# wifiuart_03_12_2018.net
KiCad netlist of a schematic drawn in EAGLE
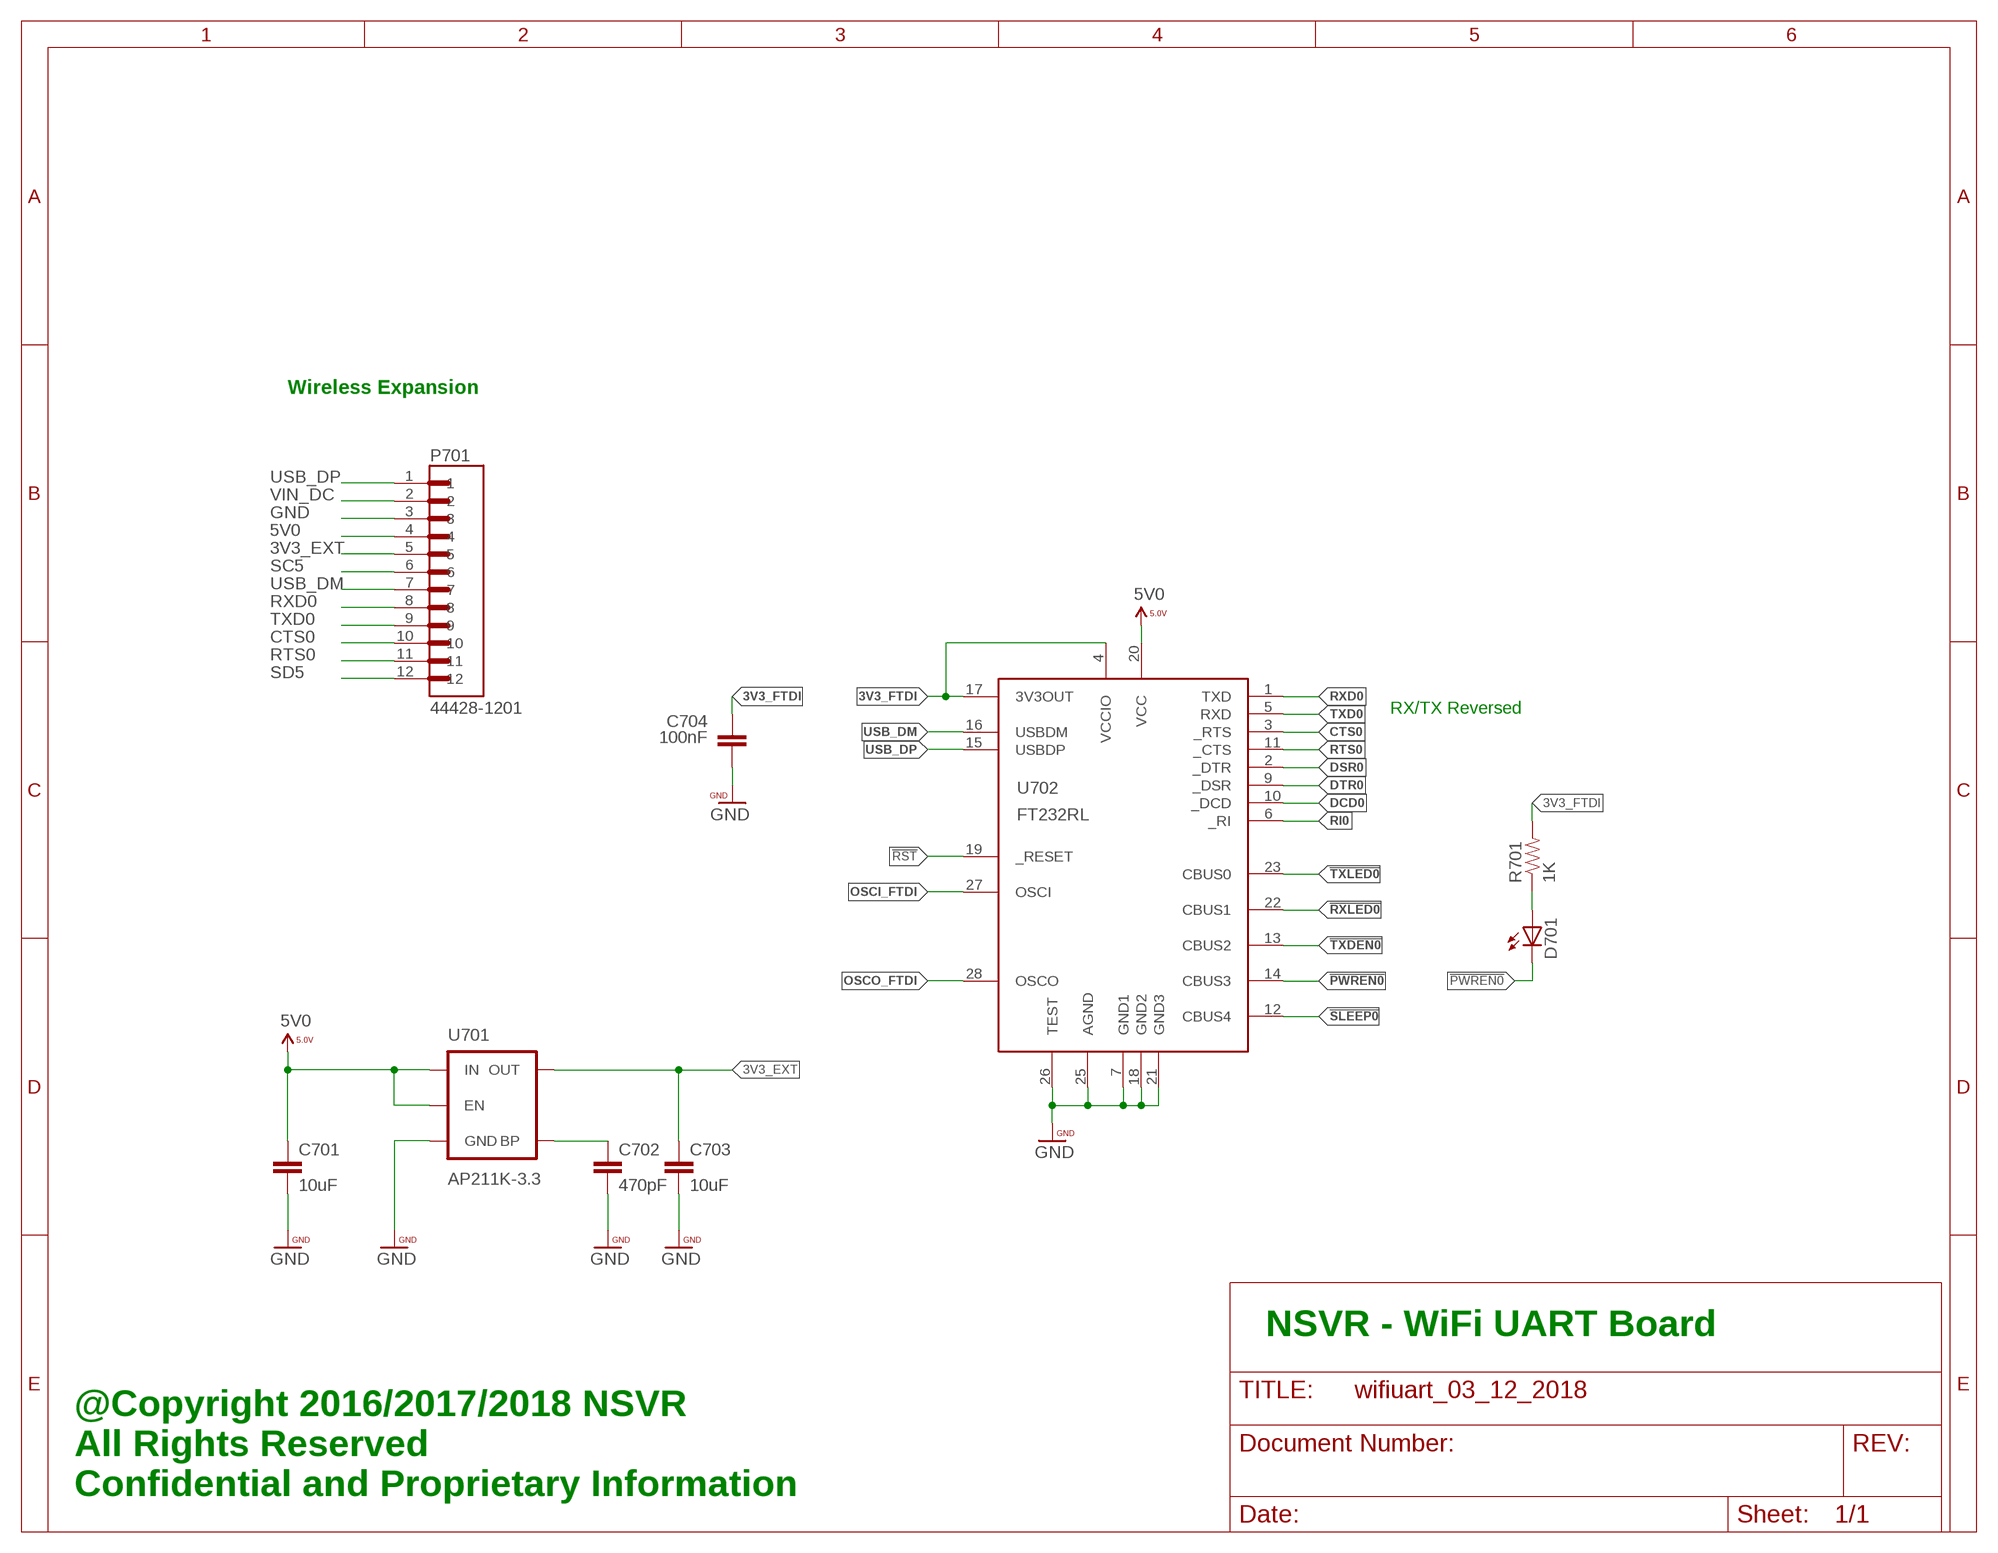
[diagram p0: schematic, sheet 1]

(export (version "E")
  (design (tool "Eeschema 10.0.6"))
  (components
    (comp (ref "C701")
      (value "10uF")
      (footprint "eagle-import:0603-CAP")
      (libsource (lib "eagle-import") (part "CAP0603-CAP"))
    )
    (comp (ref "C702")
      (value "470pF")
      (footprint "eagle-import:0402-CAP")
      (libsource (lib "eagle-import") (part "CAP0402-CAP"))
    )
    (comp (ref "C703")
      (value "10uF")
      (footprint "eagle-import:0603-CAP")
      (libsource (lib "eagle-import") (part "CAP0603-CAP"))
    )
    (comp (ref "C704")
      (value "100nF")
      (footprint "eagle-import:0402-CAP")
      (libsource (lib "eagle-import") (part "CAP0402-CAP"))
    )
    (comp (ref "D701")
      (value "LEDCHIP-LED0603")
      (footprint "eagle-import:CHIP-LED0603")
      (libsource (lib "eagle-import") (part "LEDCHIP-LED0603"))
    )
    (comp (ref "P701")
      (value "44428-1201")
      (footprint "eagle-import:MOLEX_44428-1201")
      (fields (field (name "MF") "Molex"))
      (libsource (lib "eagle-import") (part "44428-1201"))
    )
    (comp (ref "R701")
      (value "1K")
      (footprint "eagle-import:EIA-0402")
      (libsource (lib "eagle-import") (part "RESISTOR0402-TYP"))
    )
    (comp (ref "U701")
      (value "AP211K-3.3")
      (footprint "eagle-import:SOT23-5")
      (libsource (lib "eagle-import") (part "V_REG_MIC52053.3V"))
    )
    (comp (ref "U702")
      (value "FT232RL")
      (footprint "eagle-import:SSOP28DB")
      (libsource (lib "eagle-import") (part "FT232RL"))
    )
  )
  (nets
    (net (code "1") (name "/SC5") (class "Default")
      (node (ref "P701") (pin "6") (pinfunction "6_6") (pintype "passive"))
    )
    (net (code "2") (name "/SD5") (class "Default")
      (node (ref "P701") (pin "12") (pinfunction "12_12") (pintype "passive"))
    )
    (net (code "3") (name "/VIN_DC") (class "Default")
      (node (ref "P701") (pin "2") (pinfunction "2_2") (pintype "passive"))
    )
    (net (code "4") (name "/~{PWREN0}") (class "Default")
      (node (ref "D701") (pin "C") (pinfunction "C_C") (pintype "passive"))
      (node (ref "U702") (pin "14") (pinfunction "CBUS3_14") (pintype "bidirectional"))
    )
    (net (code "5") (name "/~{RST}") (class "Default")
      (node (ref "U702") (pin "19") (pinfunction "_RESET_19") (pintype "input"))
    )
    (net (code "6") (name "/~{RXLED0}") (class "Default")
      (node (ref "U702") (pin "22") (pinfunction "CBUS1_22") (pintype "bidirectional"))
    )
    (net (code "7") (name "/~{SLEEP0}") (class "Default")
      (node (ref "U702") (pin "12") (pinfunction "CBUS4_12") (pintype "bidirectional"))
    )
    (net (code "8") (name "/~{TXDEN0}") (class "Default")
      (node (ref "U702") (pin "13") (pinfunction "CBUS2_13") (pintype "bidirectional"))
    )
    (net (code "9") (name "/~{TXLED0}") (class "Default")
      (node (ref "U702") (pin "23") (pinfunction "CBUS0_23") (pintype "bidirectional"))
    )
    (net (code "10") (name "3V3_EXT") (class "Default")
      (node (ref "C703") (pin "1") (pinfunction "1_1") (pintype "passive"))
      (node (ref "P701") (pin "5") (pinfunction "5_5") (pintype "passive"))
      (node (ref "U701") (pin "5") (pinfunction "OUT_5") (pintype "passive"))
    )
    (net (code "11") (name "3V3_FTDI") (class "Default")
      (node (ref "C704") (pin "1") (pinfunction "1_1") (pintype "passive"))
      (node (ref "R701") (pin "2") (pinfunction "2_2") (pintype "passive"))
      (node (ref "U702") (pin "17") (pinfunction "3V3OUT_17") (pintype "output"))
      (node (ref "U702") (pin "4") (pinfunction "VCCIO_4") (pintype "power_in"))
    )
    (net (code "12") (name "5V0") (class "Default")
      (node (ref "C701") (pin "1") (pinfunction "1_1") (pintype "passive"))
      (node (ref "P701") (pin "4") (pinfunction "4_4") (pintype "passive"))
      (node (ref "U701") (pin "1") (pinfunction "IN_1") (pintype "input"))
      (node (ref "U701") (pin "3") (pinfunction "EN_3") (pintype "input"))
      (node (ref "U702") (pin "20") (pinfunction "VCC_20") (pintype "power_in"))
    )
    (net (code "13") (name "CTS0") (class "Default")
      (node (ref "P701") (pin "10") (pinfunction "10_10") (pintype "passive"))
      (node (ref "U702") (pin "3") (pinfunction "_RTS_3") (pintype "output"))
    )
    (net (code "14") (name "DCD0") (class "Default")
      (node (ref "U702") (pin "10") (pinfunction "_DCD_10") (pintype "input"))
    )
    (net (code "15") (name "DSR0") (class "Default")
      (node (ref "U702") (pin "2") (pinfunction "_DTR_2") (pintype "output"))
    )
    (net (code "16") (name "DTR0") (class "Default")
      (node (ref "U702") (pin "9") (pinfunction "_DSR_9") (pintype "input"))
    )
    (net (code "17") (name "GND") (class "Default")
      (node (ref "C701") (pin "2") (pinfunction "2_2") (pintype "passive"))
      (node (ref "C702") (pin "2") (pinfunction "2_2") (pintype "passive"))
      (node (ref "C703") (pin "2") (pinfunction "2_2") (pintype "passive"))
      (node (ref "C704") (pin "2") (pinfunction "2_2") (pintype "passive"))
      (node (ref "P701") (pin "3") (pinfunction "3_3") (pintype "passive"))
      (node (ref "U701") (pin "2") (pinfunction "GND_2") (pintype "input"))
      (node (ref "U702") (pin "18") (pinfunction "GND2_18") (pintype "power_in"))
      (node (ref "U702") (pin "21") (pinfunction "GND3_21") (pintype "power_in"))
      (node (ref "U702") (pin "25") (pinfunction "AGND_25") (pintype "power_in"))
      (node (ref "U702") (pin "26") (pinfunction "TEST_26") (pintype "input"))
      (node (ref "U702") (pin "7") (pinfunction "GND1_7") (pintype "power_in"))
    )
    (net (code "18") (name "Net-(D701-PadA)") (class "Default")
      (node (ref "D701") (pin "A") (pinfunction "A_A") (pintype "passive"))
      (node (ref "R701") (pin "1") (pinfunction "1_1") (pintype "passive"))
    )
    (net (code "19") (name "Net-(U701-BP)") (class "Default")
      (node (ref "C702") (pin "1") (pinfunction "1_1") (pintype "passive"))
      (node (ref "U701") (pin "4") (pinfunction "BP_4") (pintype "input"))
    )
    (net (code "20") (name "OSCI_FTDI") (class "Default")
      (node (ref "U702") (pin "27") (pinfunction "OSCI_27") (pintype "input"))
    )
    (net (code "21") (name "OSCO_FTDI") (class "Default")
      (node (ref "U702") (pin "28") (pinfunction "OSCO_28") (pintype "output"))
    )
    (net (code "22") (name "RI0") (class "Default")
      (node (ref "U702") (pin "6") (pinfunction "_RI_6") (pintype "input"))
    )
    (net (code "23") (name "RTS0") (class "Default")
      (node (ref "P701") (pin "11") (pinfunction "11_11") (pintype "passive"))
      (node (ref "U702") (pin "11") (pinfunction "_CTS_11") (pintype "input"))
    )
    (net (code "24") (name "RXD0") (class "Default")
      (node (ref "P701") (pin "8") (pinfunction "8_8") (pintype "passive"))
      (node (ref "U702") (pin "1") (pinfunction "TXD_1") (pintype "output"))
    )
    (net (code "25") (name "TXD0") (class "Default")
      (node (ref "P701") (pin "9") (pinfunction "9_9") (pintype "passive"))
      (node (ref "U702") (pin "5") (pinfunction "RXD_5") (pintype "input"))
    )
    (net (code "26") (name "USB_DM") (class "Default")
      (node (ref "P701") (pin "7") (pinfunction "7_7") (pintype "passive"))
      (node (ref "U702") (pin "16") (pinfunction "USBDM_16") (pintype "bidirectional"))
    )
    (net (code "27") (name "USB_DP") (class "Default")
      (node (ref "P701") (pin "1") (pinfunction "1_1") (pintype "passive"))
      (node (ref "U702") (pin "15") (pinfunction "USBDP_15") (pintype "bidirectional"))
    )
  )
)
